# RNode.net
KiCad netlist of a schematic drawn in EAGLE
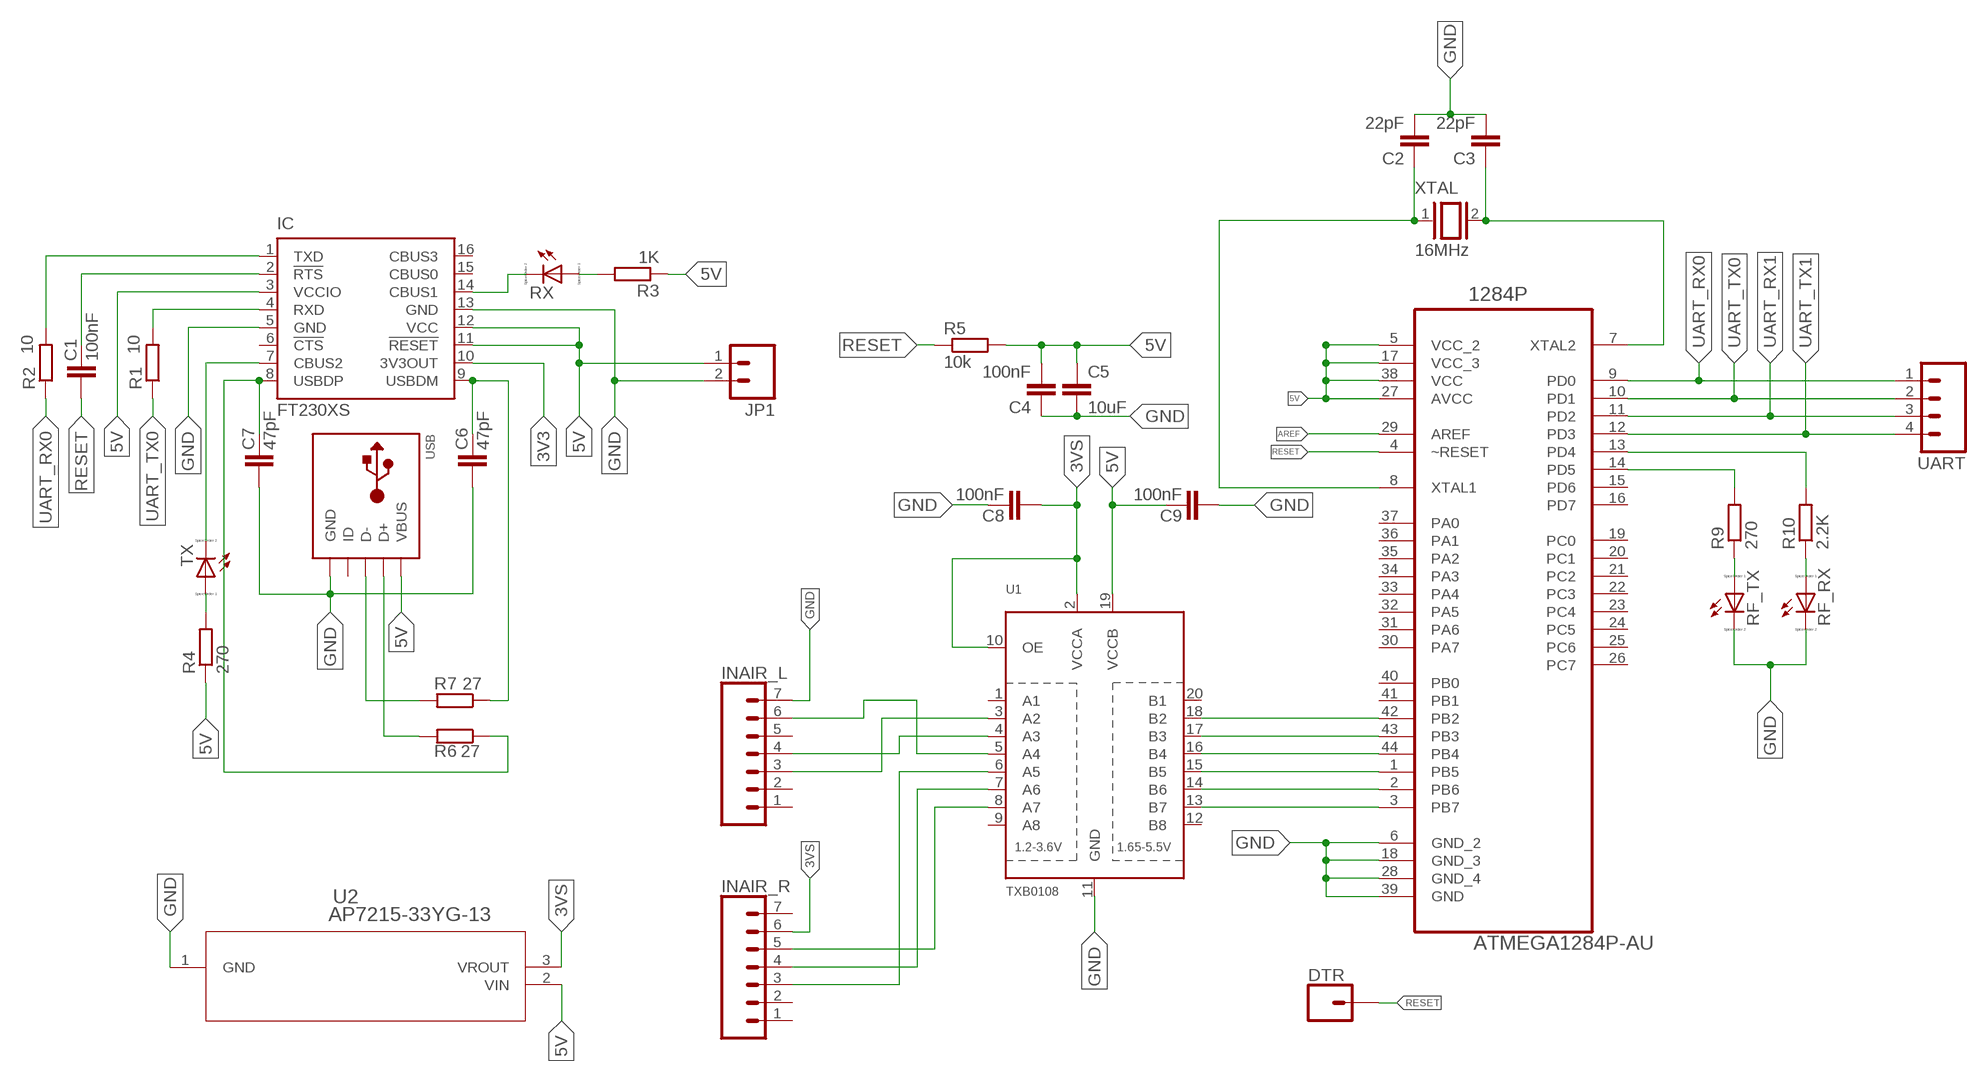
[diagram p0: schematic, sheet 1]

(export (version "E")
  (design (tool "Eeschema 10.0.6"))
  (components
    (comp (ref "1284P")
      (value "ATMEGA1284P-AU")
      (footprint "eagle-import:QFP80P1200X1200X120-44N")
      (libsource (lib "eagle-import") (part "ATMEGA1284P-AU"))
    )
    (comp (ref "C1")
      (value "100nF")
      (footprint "eagle-import:C0603")
      (libsource (lib "eagle-import") (part "C-EUC0603"))
    )
    (comp (ref "C2")
      (value "22pF")
      (footprint "eagle-import:C0603")
      (libsource (lib "eagle-import") (part "C-EUC0603"))
    )
    (comp (ref "C3")
      (value "22pF")
      (footprint "eagle-import:C0603")
      (libsource (lib "eagle-import") (part "C-EUC0603"))
    )
    (comp (ref "C4")
      (value "100nF")
      (footprint "eagle-import:C0603")
      (libsource (lib "eagle-import") (part "C-EUC0603"))
    )
    (comp (ref "C5")
      (value "10uF")
      (footprint "eagle-import:C0805")
      (libsource (lib "eagle-import") (part "C-EUC0805"))
    )
    (comp (ref "C6")
      (value "47pF")
      (footprint "eagle-import:C0603")
      (libsource (lib "eagle-import") (part "C-EUC0603"))
    )
    (comp (ref "C7")
      (value "47pF")
      (footprint "eagle-import:C0603")
      (libsource (lib "eagle-import") (part "C-EUC0603"))
    )
    (comp (ref "C8")
      (value "100nF")
      (footprint "eagle-import:C0603")
      (libsource (lib "eagle-import") (part "C-EUC0603"))
    )
    (comp (ref "C9")
      (value "100nF")
      (footprint "eagle-import:C0603")
      (libsource (lib "eagle-import") (part "C-EUC0603"))
    )
    (comp (ref "DTR")
      (value "CONN_01")
      (footprint "eagle-import:1X01")
      (libsource (lib "eagle-import") (part "CONN_01"))
    )
    (comp (ref "IC")
      (value "FT230XS")
      (footprint "eagle-import:SSOP16")
      (libsource (lib "eagle-import") (part "FT230XS"))
    )
    (comp (ref "INAIR_L")
      (value "CONN_07")
      (footprint "eagle-import:1X07")
      (libsource (lib "eagle-import") (part "CONN_07"))
    )
    (comp (ref "INAIR_R")
      (value "CONN_07")
      (footprint "eagle-import:1X07")
      (libsource (lib "eagle-import") (part "CONN_07"))
    )
    (comp (ref "JP1")
      (value "M02PTH")
      (footprint "eagle-import:1X02")
      (libsource (lib "eagle-import") (part "M02PTH"))
    )
    (comp (ref "R1")
      (value "10")
      (footprint "eagle-import:R0603")
      (libsource (lib "eagle-import") (part "R-EU_R0603"))
    )
    (comp (ref "R2")
      (value "10")
      (footprint "eagle-import:R0603")
      (libsource (lib "eagle-import") (part "R-EU_R0603"))
    )
    (comp (ref "R3")
      (value "1K")
      (footprint "eagle-import:R0603")
      (libsource (lib "eagle-import") (part "R-EU_R0603"))
    )
    (comp (ref "R4")
      (value "270")
      (footprint "eagle-import:R0603")
      (libsource (lib "eagle-import") (part "R-EU_R0603"))
    )
    (comp (ref "R5")
      (value "10k")
      (footprint "eagle-import:R0603")
      (libsource (lib "eagle-import") (part "R-EU_R0603"))
    )
    (comp (ref "R6")
      (value "27")
      (footprint "eagle-import:R0603")
      (libsource (lib "eagle-import") (part "R-EU_R0603"))
    )
    (comp (ref "R7")
      (value "27")
      (footprint "eagle-import:R0603")
      (libsource (lib "eagle-import") (part "R-EU_R0603"))
    )
    (comp (ref "R9")
      (value "270")
      (footprint "eagle-import:R0603")
      (libsource (lib "eagle-import") (part "R-EU_R0603"))
    )
    (comp (ref "R10")
      (value "2.2K")
      (footprint "eagle-import:R0603")
      (libsource (lib "eagle-import") (part "R-EU_R0603"))
    )
    (comp (ref "RF_RX")
      (value "LED_ESML0603")
      (footprint "eagle-import:LED_SML0603")
      (libsource (lib "eagle-import") (part "LED_ESML0603"))
    )
    (comp (ref "RF_TX")
      (value "LED_ESML0603")
      (footprint "eagle-import:LED_SML0603")
      (libsource (lib "eagle-import") (part "LED_ESML0603"))
    )
    (comp (ref "RX")
      (value "LED_ESML0603")
      (footprint "eagle-import:LED_SML0603")
      (libsource (lib "eagle-import") (part "LED_ESML0603"))
    )
    (comp (ref "TX")
      (value "LED_ESML0603")
      (footprint "eagle-import:LED_SML0603")
      (libsource (lib "eagle-import") (part "LED_ESML0603"))
    )
    (comp (ref "U1")
      (value "TXB0108")
      (footprint "eagle-import:TSSOP20")
      (libsource (lib "eagle-import") (part "TXB0108PWR"))
    )
    (comp (ref "U2")
      (value "AP7215-33YG-13")
      (footprint "eagle-import:SOT89-3L")
      (fields (field (name "MANUFACTURER_PART_NUMBER") "AP721533YG13"))
      (libsource (lib "eagle-import") (part "AP7215-33YG-13"))
    )
    (comp (ref "UART")
      (value "M04PTH")
      (footprint "eagle-import:1X04")
      (libsource (lib "eagle-import") (part "M04PTH"))
    )
    (comp (ref "USB")
      (value "USBMOLEX")
      (footprint "eagle-import:USB-MINIB-THM-MOLEX")
      (libsource (lib "eagle-import") (part "USBMOLEX"))
    )
    (comp (ref "XTAL")
      (value "16MHz")
      (footprint "eagle-import:QS")
      (libsource (lib "eagle-import") (part "XTAL/S"))
    )
  )
  (nets
    (net (code "1") (name "3V3") (class "Default")
      (node (ref "IC") (pin "10") (pinfunction "3V3OUT_10") (pintype "output"))
    )
    (net (code "2") (name "3VS") (class "Default")
      (node (ref "C8") (pin "1") (pinfunction "1_1") (pintype "passive"))
      (node (ref "INAIR_R") (pin "6") (pinfunction "6_6") (pintype "passive"))
      (node (ref "U1") (pin "10") (pinfunction "OE_10") (pintype "bidirectional"))
      (node (ref "U1") (pin "2") (pinfunction "VCCA_2") (pintype "bidirectional"))
      (node (ref "U2") (pin "3") (pinfunction "VROUT_3") (pintype "output"))
    )
    (net (code "3") (name "5V") (class "Default")
      (node (ref "1284P") (pin "17") (pinfunction "VCC_3_17") (pintype "power_in"))
      (node (ref "1284P") (pin "27") (pinfunction "AVCC_27") (pintype "power_in"))
      (node (ref "1284P") (pin "38") (pinfunction "VCC_38") (pintype "power_in"))
      (node (ref "1284P") (pin "5") (pinfunction "VCC_2_5") (pintype "power_in"))
      (node (ref "C4") (pin "2") (pinfunction "2_2") (pintype "passive"))
      (node (ref "C5") (pin "1") (pinfunction "1_1") (pintype "passive"))
      (node (ref "C9") (pin "2") (pinfunction "2_2") (pintype "passive"))
      (node (ref "IC") (pin "11") (pinfunction "~{RESET}_11") (pintype "input"))
      (node (ref "IC") (pin "12") (pinfunction "VCC_12") (pintype "power_in"))
      (node (ref "IC") (pin "3") (pinfunction "VCCIO_3") (pintype "power_in"))
      (node (ref "JP1") (pin "1") (pinfunction "1_1") (pintype "passive"))
      (node (ref "R3") (pin "1") (pinfunction "1_1") (pintype "passive"))
      (node (ref "R4") (pin "1") (pinfunction "1_1") (pintype "passive"))
      (node (ref "R5") (pin "2") (pinfunction "2_2") (pintype "passive"))
      (node (ref "U1") (pin "19") (pinfunction "VCCB_19") (pintype "bidirectional"))
      (node (ref "U2") (pin "2") (pinfunction "VIN_2") (pintype "input"))
      (node (ref "USB") (pin "VBUS") (pinfunction "VBUS_VBUS") (pintype "power_in"))
    )
    (net (code "4") (name "AREF") (class "Default")
      (node (ref "1284P") (pin "29") (pinfunction "AREF_29") (pintype "input"))
    )
    (net (code "5") (name "GND") (class "Default")
      (node (ref "1284P") (pin "18") (pinfunction "GND_3_18") (pintype "passive"))
      (node (ref "1284P") (pin "28") (pinfunction "GND_4_28") (pintype "passive"))
      (node (ref "1284P") (pin "39") (pinfunction "GND_39") (pintype "passive"))
      (node (ref "1284P") (pin "6") (pinfunction "GND_2_6") (pintype "passive"))
      (node (ref "C2") (pin "2") (pinfunction "2_2") (pintype "passive"))
      (node (ref "C3") (pin "2") (pinfunction "2_2") (pintype "passive"))
      (node (ref "C4") (pin "1") (pinfunction "1_1") (pintype "passive"))
      (node (ref "C5") (pin "2") (pinfunction "2_2") (pintype "passive"))
      (node (ref "C6") (pin "1") (pinfunction "1_1") (pintype "passive"))
      (node (ref "C7") (pin "1") (pinfunction "1_1") (pintype "passive"))
      (node (ref "C8") (pin "2") (pinfunction "2_2") (pintype "passive"))
      (node (ref "C9") (pin "1") (pinfunction "1_1") (pintype "passive"))
      (node (ref "IC") (pin "13") (pinfunction "GND_13") (pintype "power_in"))
      (node (ref "IC") (pin "5") (pinfunction "GND_5") (pintype "power_in"))
      (node (ref "INAIR_L") (pin "7") (pinfunction "7_7") (pintype "passive"))
      (node (ref "JP1") (pin "2") (pinfunction "2_2") (pintype "passive"))
      (node (ref "RF_RX") (pin "C") (pinfunction "C_C") (pintype "passive"))
      (node (ref "RF_TX") (pin "C") (pinfunction "C_C") (pintype "passive"))
      (node (ref "U1") (pin "11") (pinfunction "GND_11") (pintype "bidirectional"))
      (node (ref "U2") (pin "1") (pinfunction "GND_1") (pintype "power_in"))
      (node (ref "USB") (pin "GND") (pinfunction "GND_GND") (pintype "power_in"))
    )
    (net (code "6") (name "Net-(1284P-PB2)") (class "Default")
      (node (ref "1284P") (pin "42") (pinfunction "PB2_42") (pintype "bidirectional"))
      (node (ref "U1") (pin "18") (pinfunction "B2_18") (pintype "bidirectional"))
    )
    (net (code "7") (name "Net-(1284P-PB3)") (class "Default")
      (node (ref "1284P") (pin "43") (pinfunction "PB3_43") (pintype "bidirectional"))
      (node (ref "U1") (pin "17") (pinfunction "B3_17") (pintype "bidirectional"))
    )
    (net (code "8") (name "Net-(1284P-PB4)") (class "Default")
      (node (ref "1284P") (pin "44") (pinfunction "PB4_44") (pintype "bidirectional"))
      (node (ref "U1") (pin "16") (pinfunction "B4_16") (pintype "bidirectional"))
    )
    (net (code "9") (name "Net-(1284P-PB5)") (class "Default")
      (node (ref "1284P") (pin "1") (pinfunction "PB5_1") (pintype "bidirectional"))
      (node (ref "U1") (pin "15") (pinfunction "B5_15") (pintype "bidirectional"))
    )
    (net (code "10") (name "Net-(1284P-PB6)") (class "Default")
      (node (ref "1284P") (pin "2") (pinfunction "PB6_2") (pintype "bidirectional"))
      (node (ref "U1") (pin "14") (pinfunction "B6_14") (pintype "bidirectional"))
    )
    (net (code "11") (name "Net-(1284P-PB7)") (class "Default")
      (node (ref "1284P") (pin "3") (pinfunction "PB7_3") (pintype "bidirectional"))
      (node (ref "U1") (pin "13") (pinfunction "B7_13") (pintype "bidirectional"))
    )
    (net (code "12") (name "Net-(1284P-PD4)") (class "Default")
      (node (ref "1284P") (pin "13") (pinfunction "PD4_13") (pintype "bidirectional"))
      (node (ref "R10") (pin "2") (pinfunction "2_2") (pintype "passive"))
    )
    (net (code "13") (name "Net-(1284P-PD5)") (class "Default")
      (node (ref "1284P") (pin "14") (pinfunction "PD5_14") (pintype "bidirectional"))
      (node (ref "R9") (pin "2") (pinfunction "2_2") (pintype "passive"))
    )
    (net (code "14") (name "Net-(1284P-XTAL1)") (class "Default")
      (node (ref "1284P") (pin "8") (pinfunction "XTAL1_8") (pintype "input"))
      (node (ref "C2") (pin "1") (pinfunction "1_1") (pintype "passive"))
      (node (ref "XTAL") (pin "1") (pinfunction "1_1") (pintype "passive"))
    )
    (net (code "15") (name "Net-(1284P-XTAL2)") (class "Default")
      (node (ref "1284P") (pin "7") (pinfunction "XTAL2_7") (pintype "output"))
      (node (ref "C3") (pin "1") (pinfunction "1_1") (pintype "passive"))
      (node (ref "XTAL") (pin "2") (pinfunction "2_2") (pintype "passive"))
    )
    (net (code "16") (name "Net-(IC-CBUS1)") (class "Default")
      (node (ref "IC") (pin "14") (pinfunction "CBUS1_14") (pintype "bidirectional"))
      (node (ref "RX") (pin "C") (pinfunction "C_C") (pintype "passive"))
    )
    (net (code "17") (name "Net-(IC-CBUS2)") (class "Default")
      (node (ref "IC") (pin "7") (pinfunction "CBUS2_7") (pintype "bidirectional"))
      (node (ref "TX") (pin "C") (pinfunction "C_C") (pintype "passive"))
    )
    (net (code "18") (name "Net-(IC-RXD)") (class "Default")
      (node (ref "IC") (pin "4") (pinfunction "RXD_4") (pintype "input"))
      (node (ref "R1") (pin "2") (pinfunction "2_2") (pintype "passive"))
    )
    (net (code "19") (name "Net-(IC-TXD)") (class "Default")
      (node (ref "IC") (pin "1") (pinfunction "TXD_1") (pintype "output"))
      (node (ref "R2") (pin "2") (pinfunction "2_2") (pintype "passive"))
    )
    (net (code "20") (name "Net-(IC-USBDM)") (class "Default")
      (node (ref "C6") (pin "2") (pinfunction "2_2") (pintype "passive"))
      (node (ref "IC") (pin "9") (pinfunction "USBDM_9") (pintype "input"))
      (node (ref "R7") (pin "1") (pinfunction "1_1") (pintype "passive"))
    )
    (net (code "21") (name "Net-(IC-USBDP)") (class "Default")
      (node (ref "C7") (pin "2") (pinfunction "2_2") (pintype "passive"))
      (node (ref "IC") (pin "8") (pinfunction "USBDP_8") (pintype "input"))
      (node (ref "R6") (pin "1") (pinfunction "1_1") (pintype "passive"))
    )
    (net (code "22") (name "Net-(IC-~{RTS})") (class "Default")
      (node (ref "C1") (pin "2") (pinfunction "2_2") (pintype "passive"))
      (node (ref "IC") (pin "2") (pinfunction "~{RTS}_2") (pintype "output"))
    )
    (net (code "23") (name "Net-(R3-Pad2)") (class "Default")
      (node (ref "R3") (pin "2") (pinfunction "2_2") (pintype "passive"))
      (node (ref "RX") (pin "A") (pinfunction "A_A") (pintype "passive"))
    )
    (net (code "24") (name "Net-(R4-Pad2)") (class "Default")
      (node (ref "R4") (pin "2") (pinfunction "2_2") (pintype "passive"))
      (node (ref "TX") (pin "A") (pinfunction "A_A") (pintype "passive"))
    )
    (net (code "25") (name "Net-(R6-Pad2)") (class "Default")
      (node (ref "R6") (pin "2") (pinfunction "2_2") (pintype "passive"))
      (node (ref "USB") (pin "D+") (pinfunction "D+_D+") (pintype "bidirectional"))
    )
    (net (code "26") (name "Net-(R7-Pad2)") (class "Default")
      (node (ref "R7") (pin "2") (pinfunction "2_2") (pintype "passive"))
      (node (ref "USB") (pin "D-") (pinfunction "D-_D-") (pintype "bidirectional"))
    )
    (net (code "27") (name "Net-(R9-Pad1)") (class "Default")
      (node (ref "R9") (pin "1") (pinfunction "1_1") (pintype "passive"))
      (node (ref "RF_TX") (pin "A") (pinfunction "A_A") (pintype "passive"))
    )
    (net (code "28") (name "Net-(R10-Pad1)") (class "Default")
      (node (ref "R10") (pin "1") (pinfunction "1_1") (pintype "passive"))
      (node (ref "RF_RX") (pin "A") (pinfunction "A_A") (pintype "passive"))
    )
    (net (code "29") (name "Net-(U1-A2)") (class "Default")
      (node (ref "INAIR_L") (pin "3") (pinfunction "3_3") (pintype "passive"))
      (node (ref "U1") (pin "3") (pinfunction "A2_3") (pintype "bidirectional"))
    )
    (net (code "30") (name "Net-(U1-A3)") (class "Default")
      (node (ref "INAIR_L") (pin "4") (pinfunction "4_4") (pintype "passive"))
      (node (ref "U1") (pin "4") (pinfunction "A3_4") (pintype "bidirectional"))
    )
    (net (code "31") (name "Net-(U1-A4)") (class "Default")
      (node (ref "INAIR_L") (pin "6") (pinfunction "6_6") (pintype "passive"))
      (node (ref "U1") (pin "5") (pinfunction "A4_5") (pintype "bidirectional"))
    )
    (net (code "32") (name "Net-(U1-A5)") (class "Default")
      (node (ref "INAIR_R") (pin "3") (pinfunction "3_3") (pintype "passive"))
      (node (ref "U1") (pin "6") (pinfunction "A5_6") (pintype "bidirectional"))
    )
    (net (code "33") (name "Net-(U1-A6)") (class "Default")
      (node (ref "INAIR_R") (pin "4") (pinfunction "4_4") (pintype "passive"))
      (node (ref "U1") (pin "7") (pinfunction "A6_7") (pintype "bidirectional"))
    )
    (net (code "34") (name "Net-(U1-A7)") (class "Default")
      (node (ref "INAIR_R") (pin "5") (pinfunction "5_5") (pintype "passive"))
      (node (ref "U1") (pin "8") (pinfunction "A7_8") (pintype "bidirectional"))
    )
    (net (code "35") (name "RESET") (class "Default")
      (node (ref "1284P") (pin "4") (pinfunction "~{RESET}_4") (pintype "input"))
      (node (ref "C1") (pin "1") (pinfunction "1_1") (pintype "passive"))
      (node (ref "DTR") (pin "1") (pinfunction "1_1") (pintype "passive"))
      (node (ref "R5") (pin "1") (pinfunction "1_1") (pintype "passive"))
    )
    (net (code "36") (name "UART_RX0") (class "Default")
      (node (ref "1284P") (pin "9") (pinfunction "PD0_9") (pintype "bidirectional"))
      (node (ref "R2") (pin "1") (pinfunction "1_1") (pintype "passive"))
      (node (ref "UART") (pin "1") (pinfunction "1_1") (pintype "passive"))
    )
    (net (code "37") (name "UART_RX1") (class "Default")
      (node (ref "1284P") (pin "11") (pinfunction "PD2_11") (pintype "bidirectional"))
      (node (ref "UART") (pin "3") (pinfunction "3_3") (pintype "passive"))
    )
    (net (code "38") (name "UART_TX0") (class "Default")
      (node (ref "1284P") (pin "10") (pinfunction "PD1_10") (pintype "bidirectional"))
      (node (ref "R1") (pin "1") (pinfunction "1_1") (pintype "passive"))
      (node (ref "UART") (pin "2") (pinfunction "2_2") (pintype "passive"))
    )
    (net (code "39") (name "UART_TX1") (class "Default")
      (node (ref "1284P") (pin "12") (pinfunction "PD3_12") (pintype "bidirectional"))
      (node (ref "UART") (pin "4") (pinfunction "4_4") (pintype "passive"))
    )
    (net (code "40") (name "unconnected-(1284P-PA0-Pad37)") (class "Default")
      (node (ref "1284P") (pin "37") (pinfunction "PA0_37") (pintype "bidirectional"))
    )
    (net (code "41") (name "unconnected-(1284P-PA1-Pad36)") (class "Default")
      (node (ref "1284P") (pin "36") (pinfunction "PA1_36") (pintype "bidirectional"))
    )
    (net (code "42") (name "unconnected-(1284P-PA2-Pad35)") (class "Default")
      (node (ref "1284P") (pin "35") (pinfunction "PA2_35") (pintype "bidirectional"))
    )
    (net (code "43") (name "unconnected-(1284P-PA3-Pad34)") (class "Default")
      (node (ref "1284P") (pin "34") (pinfunction "PA3_34") (pintype "bidirectional"))
    )
    (net (code "44") (name "unconnected-(1284P-PA4-Pad33)") (class "Default")
      (node (ref "1284P") (pin "33") (pinfunction "PA4_33") (pintype "bidirectional"))
    )
    (net (code "45") (name "unconnected-(1284P-PA5-Pad32)") (class "Default")
      (node (ref "1284P") (pin "32") (pinfunction "PA5_32") (pintype "bidirectional"))
    )
    (net (code "46") (name "unconnected-(1284P-PA6-Pad31)") (class "Default")
      (node (ref "1284P") (pin "31") (pinfunction "PA6_31") (pintype "bidirectional"))
    )
    (net (code "47") (name "unconnected-(1284P-PA7-Pad30)") (class "Default")
      (node (ref "1284P") (pin "30") (pinfunction "PA7_30") (pintype "bidirectional"))
    )
    (net (code "48") (name "unconnected-(1284P-PB0-Pad40)") (class "Default")
      (node (ref "1284P") (pin "40") (pinfunction "PB0_40") (pintype "bidirectional"))
    )
    (net (code "49") (name "unconnected-(1284P-PB1-Pad41)") (class "Default")
      (node (ref "1284P") (pin "41") (pinfunction "PB1_41") (pintype "bidirectional"))
    )
    (net (code "50") (name "unconnected-(1284P-PC0-Pad19)") (class "Default")
      (node (ref "1284P") (pin "19") (pinfunction "PC0_19") (pintype "bidirectional"))
    )
    (net (code "51") (name "unconnected-(1284P-PC1-Pad20)") (class "Default")
      (node (ref "1284P") (pin "20") (pinfunction "PC1_20") (pintype "bidirectional"))
    )
    (net (code "52") (name "unconnected-(1284P-PC2-Pad21)") (class "Default")
      (node (ref "1284P") (pin "21") (pinfunction "PC2_21") (pintype "bidirectional"))
    )
    (net (code "53") (name "unconnected-(1284P-PC3-Pad22)") (class "Default")
      (node (ref "1284P") (pin "22") (pinfunction "PC3_22") (pintype "bidirectional"))
    )
    (net (code "54") (name "unconnected-(1284P-PC4-Pad23)") (class "Default")
      (node (ref "1284P") (pin "23") (pinfunction "PC4_23") (pintype "bidirectional"))
    )
    (net (code "55") (name "unconnected-(1284P-PC5-Pad24)") (class "Default")
      (node (ref "1284P") (pin "24") (pinfunction "PC5_24") (pintype "bidirectional"))
    )
    (net (code "56") (name "unconnected-(1284P-PC6-Pad25)") (class "Default")
      (node (ref "1284P") (pin "25") (pinfunction "PC6_25") (pintype "bidirectional"))
    )
    (net (code "57") (name "unconnected-(1284P-PC7-Pad26)") (class "Default")
      (node (ref "1284P") (pin "26") (pinfunction "PC7_26") (pintype "bidirectional"))
    )
    (net (code "58") (name "unconnected-(1284P-PD6-Pad15)") (class "Default")
      (node (ref "1284P") (pin "15") (pinfunction "PD6_15") (pintype "bidirectional"))
    )
    (net (code "59") (name "unconnected-(1284P-PD7-Pad16)") (class "Default")
      (node (ref "1284P") (pin "16") (pinfunction "PD7_16") (pintype "bidirectional"))
    )
    (net (code "60") (name "unconnected-(IC-CBUS0-Pad15)") (class "Default")
      (node (ref "IC") (pin "15") (pinfunction "CBUS0_15") (pintype "bidirectional"))
    )
    (net (code "61") (name "unconnected-(IC-CBUS3-Pad16)") (class "Default")
      (node (ref "IC") (pin "16") (pinfunction "CBUS3_16") (pintype "bidirectional"))
    )
    (net (code "62") (name "unconnected-(IC-~{CTS}-Pad6)") (class "Default")
      (node (ref "IC") (pin "6") (pinfunction "~{CTS}_6") (pintype "input"))
    )
    (net (code "63") (name "unconnected-(INAIR_L-Pad1)") (class "Default")
      (node (ref "INAIR_L") (pin "1") (pinfunction "1_1") (pintype "passive"))
    )
    (net (code "64") (name "unconnected-(INAIR_L-Pad2)") (class "Default")
      (node (ref "INAIR_L") (pin "2") (pinfunction "2_2") (pintype "passive"))
    )
    (net (code "65") (name "unconnected-(INAIR_L-Pad5)") (class "Default")
      (node (ref "INAIR_L") (pin "5") (pinfunction "5_5") (pintype "passive"))
    )
    (net (code "66") (name "unconnected-(INAIR_R-Pad1)") (class "Default")
      (node (ref "INAIR_R") (pin "1") (pinfunction "1_1") (pintype "passive"))
    )
    (net (code "67") (name "unconnected-(INAIR_R-Pad2)") (class "Default")
      (node (ref "INAIR_R") (pin "2") (pinfunction "2_2") (pintype "passive"))
    )
    (net (code "68") (name "unconnected-(INAIR_R-Pad7)") (class "Default")
      (node (ref "INAIR_R") (pin "7") (pinfunction "7_7") (pintype "passive"))
    )
    (net (code "69") (name "unconnected-(U1-A1-Pad1)") (class "Default")
      (node (ref "U1") (pin "1") (pinfunction "A1_1") (pintype "bidirectional"))
    )
    (net (code "70") (name "unconnected-(U1-A8-Pad9)") (class "Default")
      (node (ref "U1") (pin "9") (pinfunction "A8_9") (pintype "bidirectional"))
    )
    (net (code "71") (name "unconnected-(U1-B1-Pad20)") (class "Default")
      (node (ref "U1") (pin "20") (pinfunction "B1_20") (pintype "bidirectional"))
    )
    (net (code "72") (name "unconnected-(U1-B8-Pad12)") (class "Default")
      (node (ref "U1") (pin "12") (pinfunction "B8_12") (pintype "bidirectional"))
    )
    (net (code "73") (name "unconnected-(USB-PadID)") (class "Default")
      (node (ref "USB") (pin "ID") (pinfunction "ID_ID") (pintype "bidirectional"))
    )
  )
)
